# FRA_bulkhead_v2.net
KiCad netlist of a schematic drawn in EAGLE
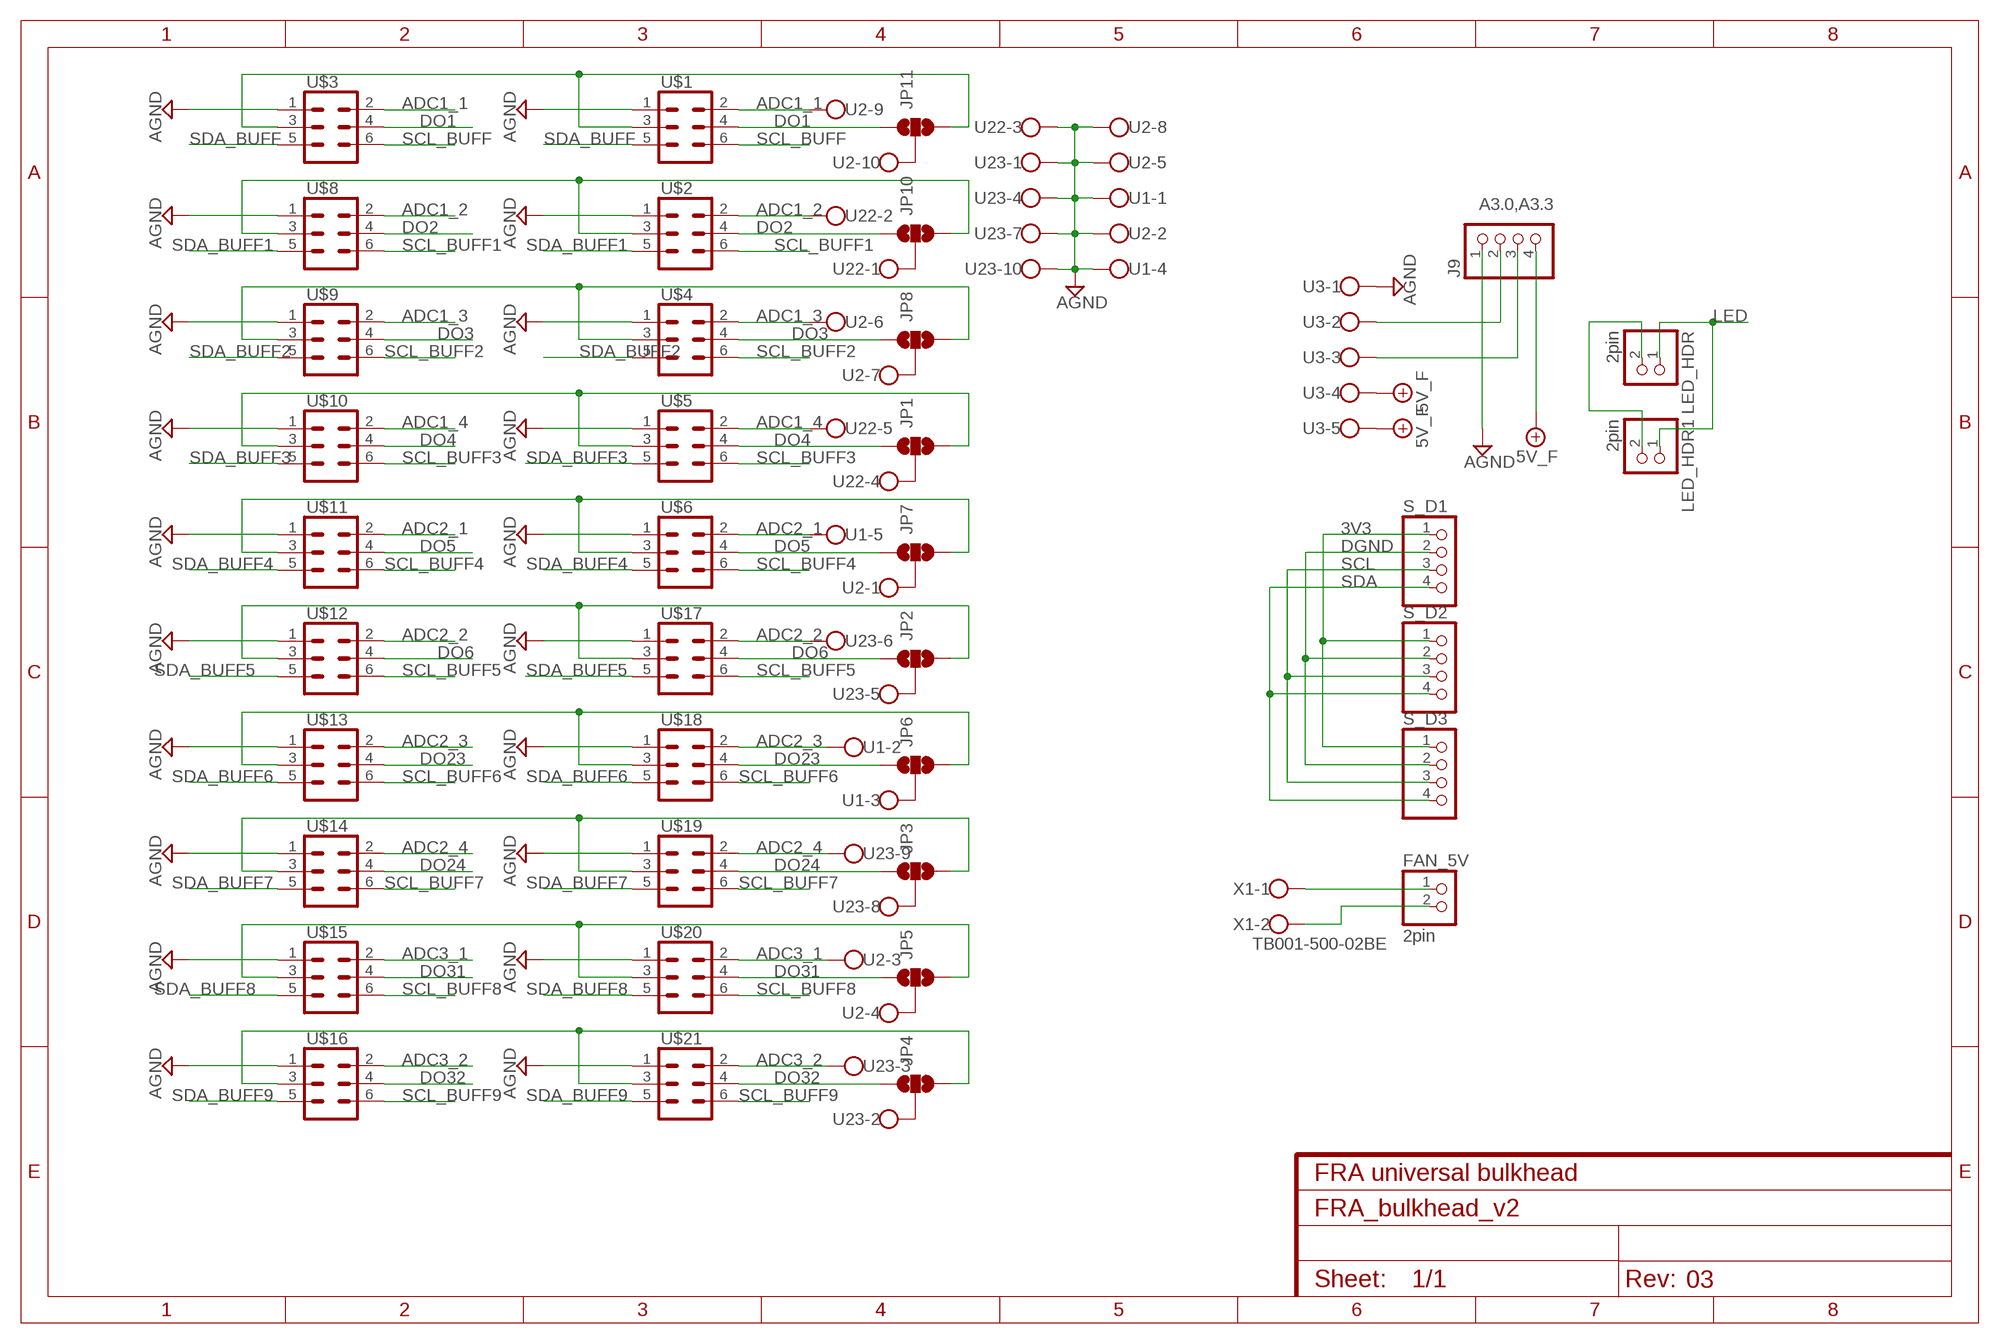
[diagram p0: schematic, sheet 1]

(export (version "E")
  (design (tool "Eeschema 10.0.6"))
  (components
    (comp (ref "FAN_5V")
      (value "2pin")
      (footprint "eagle-import:1X02")
      (fields (field (name "PARTNO") "TSW-102-07-G-S"))
      (libsource (lib "eagle-import") (part "PINHD-1X2"))
    )
    (comp (ref "J9")
      (value "4pin")
      (footprint "eagle-import:1X04")
      (fields (field (name "PARTNO") "61300411121"))
      (libsource (lib "eagle-import") (part "PINHD-1X4"))
    )
    (comp (ref "JP1")
      (value "JUMPER-SMT_3_NO_NO_SILK")
      (footprint "eagle-import:SMT-JUMPER_3_0-NO_TRACE_NO-SILK")
      (libsource (lib "eagle-import") (part "JUMPER-SMT_3_NO_NO_SILK"))
    )
    (comp (ref "JP2")
      (value "JUMPER-SMT_3_NO_NO_SILK")
      (footprint "eagle-import:SMT-JUMPER_3_0-NO_TRACE_NO-SILK")
      (libsource (lib "eagle-import") (part "JUMPER-SMT_3_NO_NO_SILK"))
    )
    (comp (ref "JP3")
      (value "JUMPER-SMT_3_NO_NO_SILK")
      (footprint "eagle-import:SMT-JUMPER_3_0-NO_TRACE_NO-SILK")
      (libsource (lib "eagle-import") (part "JUMPER-SMT_3_NO_NO_SILK"))
    )
    (comp (ref "JP4")
      (value "JUMPER-SMT_3_NO_NO_SILK")
      (footprint "eagle-import:SMT-JUMPER_3_0-NO_TRACE_NO-SILK")
      (libsource (lib "eagle-import") (part "JUMPER-SMT_3_NO_NO_SILK"))
    )
    (comp (ref "JP5")
      (value "JUMPER-SMT_3_NO_NO_SILK")
      (footprint "eagle-import:SMT-JUMPER_3_0-NO_TRACE_NO-SILK")
      (libsource (lib "eagle-import") (part "JUMPER-SMT_3_NO_NO_SILK"))
    )
    (comp (ref "JP6")
      (value "JUMPER-SMT_3_NO_NO_SILK")
      (footprint "eagle-import:SMT-JUMPER_3_0-NO_TRACE_NO-SILK")
      (libsource (lib "eagle-import") (part "JUMPER-SMT_3_NO_NO_SILK"))
    )
    (comp (ref "JP7")
      (value "JUMPER-SMT_3_NO_NO_SILK")
      (footprint "eagle-import:SMT-JUMPER_3_0-NO_TRACE_NO-SILK")
      (libsource (lib "eagle-import") (part "JUMPER-SMT_3_NO_NO_SILK"))
    )
    (comp (ref "JP8")
      (value "JUMPER-SMT_3_NO_NO_SILK")
      (footprint "eagle-import:SMT-JUMPER_3_0-NO_TRACE_NO-SILK")
      (libsource (lib "eagle-import") (part "JUMPER-SMT_3_NO_NO_SILK"))
    )
    (comp (ref "JP10")
      (value "JUMPER-SMT_3_NO_NO_SILK")
      (footprint "eagle-import:SMT-JUMPER_3_0-NO_TRACE_NO-SILK")
      (libsource (lib "eagle-import") (part "JUMPER-SMT_3_NO_NO_SILK"))
    )
    (comp (ref "JP11")
      (value "JUMPER-SMT_3_NO_NO_SILK")
      (footprint "eagle-import:SMT-JUMPER_3_0-NO_TRACE_NO-SILK")
      (libsource (lib "eagle-import") (part "JUMPER-SMT_3_NO_NO_SILK"))
    )
    (comp (ref "LED_HDR")
      (value "2pin")
      (footprint "eagle-import:1X02")
      (fields (field (name "PARTNO") "TSW-102-07-G-S"))
      (libsource (lib "eagle-import") (part "PINHD-1X2"))
    )
    (comp (ref "LED_HDR1")
      (value "2pin")
      (footprint "eagle-import:1X02")
      (fields (field (name "PARTNO") "TSW-102-07-G-S"))
      (libsource (lib "eagle-import") (part "PINHD-1X2"))
    )
    (comp (ref "S_D1")
      (value "4pin")
      (footprint "eagle-import:1X04")
      (fields (field (name "PARTNO") "61300411121"))
      (libsource (lib "eagle-import") (part "PINHD-1X4"))
    )
    (comp (ref "S_D2")
      (value "4pin")
      (footprint "eagle-import:1X04")
      (fields (field (name "PARTNO") "61300411121"))
      (libsource (lib "eagle-import") (part "PINHD-1X4"))
    )
    (comp (ref "S_D3")
      (value "4pin")
      (footprint "eagle-import:1X04")
      (fields (field (name "PARTNO") "61300411121"))
      (libsource (lib "eagle-import") (part "PINHD-1X4"))
    )
    (comp (ref "U$1")
      (value "CONN_03X2_WE_61200621621")
      (footprint "eagle-import:WE_61200621621")
      (fields (field (name "PARTNO") "61200621621"))
      (libsource (lib "eagle-import") (part "CONN_03X2_WE_61200621621"))
    )
    (comp (ref "U$2")
      (value "CONN_03X2_WE_61200621621")
      (footprint "eagle-import:WE_61200621621")
      (fields (field (name "PARTNO") "61200621621"))
      (libsource (lib "eagle-import") (part "CONN_03X2_WE_61200621621"))
    )
    (comp (ref "U$3")
      (value "CONN_03X2_WE_61200621621")
      (footprint "eagle-import:WE_61200621621")
      (fields (field (name "PARTNO") "61200621621"))
      (libsource (lib "eagle-import") (part "CONN_03X2_WE_61200621621"))
    )
    (comp (ref "U$4")
      (value "CONN_03X2_WE_61200621621")
      (footprint "eagle-import:WE_61200621621")
      (fields (field (name "PARTNO") "61200621621"))
      (libsource (lib "eagle-import") (part "CONN_03X2_WE_61200621621"))
    )
    (comp (ref "U$5")
      (value "CONN_03X2_WE_61200621621")
      (footprint "eagle-import:WE_61200621621")
      (fields (field (name "PARTNO") "61200621621"))
      (libsource (lib "eagle-import") (part "CONN_03X2_WE_61200621621"))
    )
    (comp (ref "U$6")
      (value "CONN_03X2_WE_61200621621")
      (footprint "eagle-import:WE_61200621621")
      (fields (field (name "PARTNO") "61200621621"))
      (libsource (lib "eagle-import") (part "CONN_03X2_WE_61200621621"))
    )
    (comp (ref "U$8")
      (value "CONN_03X2_WE_61200621621")
      (footprint "eagle-import:WE_61200621621")
      (fields (field (name "PARTNO") "61200621621"))
      (libsource (lib "eagle-import") (part "CONN_03X2_WE_61200621621"))
    )
    (comp (ref "U$9")
      (value "CONN_03X2_WE_61200621621")
      (footprint "eagle-import:WE_61200621621")
      (fields (field (name "PARTNO") "61200621621"))
      (libsource (lib "eagle-import") (part "CONN_03X2_WE_61200621621"))
    )
    (comp (ref "U$10")
      (value "CONN_03X2_WE_61200621621")
      (footprint "eagle-import:WE_61200621621")
      (fields (field (name "PARTNO") "61200621621"))
      (libsource (lib "eagle-import") (part "CONN_03X2_WE_61200621621"))
    )
    (comp (ref "U$11")
      (value "CONN_03X2_WE_61200621621")
      (footprint "eagle-import:WE_61200621621")
      (fields (field (name "PARTNO") "61200621621"))
      (libsource (lib "eagle-import") (part "CONN_03X2_WE_61200621621"))
    )
    (comp (ref "U$12")
      (value "CONN_03X2_WE_61200621621")
      (footprint "eagle-import:WE_61200621621")
      (fields (field (name "PARTNO") "61200621621"))
      (libsource (lib "eagle-import") (part "CONN_03X2_WE_61200621621"))
    )
    (comp (ref "U$13")
      (value "CONN_03X2_WE_61200621621")
      (footprint "eagle-import:WE_61200621621")
      (fields (field (name "PARTNO") "61200621621"))
      (libsource (lib "eagle-import") (part "CONN_03X2_WE_61200621621"))
    )
    (comp (ref "U$14")
      (value "CONN_03X2_WE_61200621621")
      (footprint "eagle-import:WE_61200621621")
      (fields (field (name "PARTNO") "61200621621"))
      (libsource (lib "eagle-import") (part "CONN_03X2_WE_61200621621"))
    )
    (comp (ref "U$15")
      (value "CONN_03X2_WE_61200621621")
      (footprint "eagle-import:WE_61200621621")
      (fields (field (name "PARTNO") "61200621621"))
      (libsource (lib "eagle-import") (part "CONN_03X2_WE_61200621621"))
    )
    (comp (ref "U$16")
      (value "CONN_03X2_WE_61200621621")
      (footprint "eagle-import:WE_61200621621")
      (fields (field (name "PARTNO") "61200621621"))
      (libsource (lib "eagle-import") (part "CONN_03X2_WE_61200621621"))
    )
    (comp (ref "U$17")
      (value "CONN_03X2_WE_61200621621")
      (footprint "eagle-import:WE_61200621621")
      (fields (field (name "PARTNO") "61200621621"))
      (libsource (lib "eagle-import") (part "CONN_03X2_WE_61200621621"))
    )
    (comp (ref "U$18")
      (value "CONN_03X2_WE_61200621621")
      (footprint "eagle-import:WE_61200621621")
      (fields (field (name "PARTNO") "61200621621"))
      (libsource (lib "eagle-import") (part "CONN_03X2_WE_61200621621"))
    )
    (comp (ref "U$19")
      (value "CONN_03X2_WE_61200621621")
      (footprint "eagle-import:WE_61200621621")
      (fields (field (name "PARTNO") "61200621621"))
      (libsource (lib "eagle-import") (part "CONN_03X2_WE_61200621621"))
    )
    (comp (ref "U$20")
      (value "CONN_03X2_WE_61200621621")
      (footprint "eagle-import:WE_61200621621")
      (fields (field (name "PARTNO") "61200621621"))
      (libsource (lib "eagle-import") (part "CONN_03X2_WE_61200621621"))
    )
    (comp (ref "U$21")
      (value "CONN_03X2_WE_61200621621")
      (footprint "eagle-import:WE_61200621621")
      (fields (field (name "PARTNO") "61200621621"))
      (libsource (lib "eagle-import") (part "CONN_03X2_WE_61200621621"))
    )
    (comp (ref "U1")
      (value "TB003V-500-P05BERIGHTANGLE-NORMAL")
      (footprint "eagle-import:TB003-500-P05BE")
      (libsource (lib "eagle-import") (part "TB003V-500-P05BERIGHTANGLE-NORMAL"))
    )
    (comp (ref "U2")
      (value "TB003V-500-P10BERIGHTANGLE-NORMAL")
      (footprint "eagle-import:TB003-500-P10BE")
      (libsource (lib "eagle-import") (part "TB003V-500-P10BERIGHTANGLE-NORMAL"))
    )
    (comp (ref "U3")
      (value "TB003V-500-P05BERIGHTANGLE-NORMAL")
      (footprint "eagle-import:TB003-500-P05BE")
      (libsource (lib "eagle-import") (part "TB003V-500-P05BERIGHTANGLE-NORMAL"))
    )
    (comp (ref "U22")
      (value "TB003V-500-P05BERIGHTANGLE-NORMAL")
      (footprint "eagle-import:TB003-500-P05BE")
      (libsource (lib "eagle-import") (part "TB003V-500-P05BERIGHTANGLE-NORMAL"))
    )
    (comp (ref "U23")
      (value "TB003V-500-P10BERIGHTANGLE-NORMAL")
      (footprint "eagle-import:TB003-500-P10BE")
      (libsource (lib "eagle-import") (part "TB003V-500-P10BERIGHTANGLE-NORMAL"))
    )
    (comp (ref "X1")
      (value "TB001-500-02BE")
      (footprint "eagle-import:W237-102")
      (fields (field (name "MPN") "237-102") (field (name "PARTNO") "TB001-500-02BE"))
      (libsource (lib "eagle-import") (part "W237-102"))
    )
  )
  (nets
    (net (code "1") (name "/3V3") (class "Default")
      (node (ref "S_D1") (pin "1") (pinfunction "1_1") (pintype "passive"))
      (node (ref "S_D2") (pin "1") (pinfunction "1_1") (pintype "passive"))
      (node (ref "S_D3") (pin "1") (pinfunction "1_1") (pintype "passive"))
    )
    (net (code "2") (name "/ADC1_1") (class "Default")
      (node (ref "U$1") (pin "2") (pinfunction "2_2") (pintype "bidirectional"))
      (node (ref "U$3") (pin "2") (pinfunction "2_2") (pintype "bidirectional"))
      (node (ref "U2") (pin "9") (pinfunction "KL_9") (pintype "passive"))
    )
    (net (code "3") (name "/ADC1_2") (class "Default")
      (node (ref "U$2") (pin "2") (pinfunction "2_2") (pintype "bidirectional"))
      (node (ref "U$8") (pin "2") (pinfunction "2_2") (pintype "bidirectional"))
      (node (ref "U22") (pin "2") (pinfunction "KL_2") (pintype "passive"))
    )
    (net (code "4") (name "/ADC1_3") (class "Default")
      (node (ref "U$4") (pin "2") (pinfunction "2_2") (pintype "bidirectional"))
      (node (ref "U$9") (pin "2") (pinfunction "2_2") (pintype "bidirectional"))
      (node (ref "U2") (pin "6") (pinfunction "KL_6") (pintype "passive"))
    )
    (net (code "5") (name "/ADC1_4") (class "Default")
      (node (ref "U$10") (pin "2") (pinfunction "2_2") (pintype "bidirectional"))
      (node (ref "U$5") (pin "2") (pinfunction "2_2") (pintype "bidirectional"))
      (node (ref "U22") (pin "5") (pinfunction "KL_5") (pintype "passive"))
    )
    (net (code "6") (name "/ADC2_1") (class "Default")
      (node (ref "U$11") (pin "2") (pinfunction "2_2") (pintype "bidirectional"))
      (node (ref "U$6") (pin "2") (pinfunction "2_2") (pintype "bidirectional"))
      (node (ref "U1") (pin "5") (pinfunction "KL_5") (pintype "passive"))
    )
    (net (code "7") (name "/ADC2_2") (class "Default")
      (node (ref "U$12") (pin "2") (pinfunction "2_2") (pintype "bidirectional"))
      (node (ref "U$17") (pin "2") (pinfunction "2_2") (pintype "bidirectional"))
      (node (ref "U23") (pin "6") (pinfunction "KL_6") (pintype "passive"))
    )
    (net (code "8") (name "/ADC2_3") (class "Default")
      (node (ref "U$13") (pin "2") (pinfunction "2_2") (pintype "bidirectional"))
      (node (ref "U$18") (pin "2") (pinfunction "2_2") (pintype "bidirectional"))
      (node (ref "U1") (pin "2") (pinfunction "KL_2") (pintype "passive"))
    )
    (net (code "9") (name "/ADC2_4") (class "Default")
      (node (ref "U$14") (pin "2") (pinfunction "2_2") (pintype "bidirectional"))
      (node (ref "U$19") (pin "2") (pinfunction "2_2") (pintype "bidirectional"))
      (node (ref "U23") (pin "9") (pinfunction "KL_9") (pintype "passive"))
    )
    (net (code "10") (name "/ADC3_1") (class "Default")
      (node (ref "U$15") (pin "2") (pinfunction "2_2") (pintype "bidirectional"))
      (node (ref "U$20") (pin "2") (pinfunction "2_2") (pintype "bidirectional"))
      (node (ref "U2") (pin "3") (pinfunction "KL_3") (pintype "passive"))
    )
    (net (code "11") (name "/ADC3_2") (class "Default")
      (node (ref "U$16") (pin "2") (pinfunction "2_2") (pintype "bidirectional"))
      (node (ref "U$21") (pin "2") (pinfunction "2_2") (pintype "bidirectional"))
      (node (ref "U23") (pin "3") (pinfunction "KL_3") (pintype "passive"))
    )
    (net (code "12") (name "/DGND") (class "Default")
      (node (ref "S_D1") (pin "2") (pinfunction "2_2") (pintype "passive"))
      (node (ref "S_D2") (pin "2") (pinfunction "2_2") (pintype "passive"))
      (node (ref "S_D3") (pin "2") (pinfunction "2_2") (pintype "passive"))
    )
    (net (code "13") (name "/DO1") (class "Default")
      (node (ref "JP11") (pin "1") (pinfunction "1_1") (pintype "passive"))
      (node (ref "U$1") (pin "4") (pinfunction "4_4") (pintype "bidirectional"))
      (node (ref "U$3") (pin "4") (pinfunction "4_4") (pintype "bidirectional"))
    )
    (net (code "14") (name "/DO2") (class "Default")
      (node (ref "JP10") (pin "1") (pinfunction "1_1") (pintype "passive"))
      (node (ref "U$2") (pin "4") (pinfunction "4_4") (pintype "bidirectional"))
      (node (ref "U$8") (pin "4") (pinfunction "4_4") (pintype "bidirectional"))
    )
    (net (code "15") (name "/DO3") (class "Default")
      (node (ref "JP8") (pin "1") (pinfunction "1_1") (pintype "passive"))
      (node (ref "U$4") (pin "4") (pinfunction "4_4") (pintype "bidirectional"))
      (node (ref "U$9") (pin "4") (pinfunction "4_4") (pintype "bidirectional"))
    )
    (net (code "16") (name "/DO4") (class "Default")
      (node (ref "JP1") (pin "1") (pinfunction "1_1") (pintype "passive"))
      (node (ref "U$10") (pin "4") (pinfunction "4_4") (pintype "bidirectional"))
      (node (ref "U$5") (pin "4") (pinfunction "4_4") (pintype "bidirectional"))
    )
    (net (code "17") (name "/DO5") (class "Default")
      (node (ref "JP7") (pin "1") (pinfunction "1_1") (pintype "passive"))
      (node (ref "U$11") (pin "4") (pinfunction "4_4") (pintype "bidirectional"))
      (node (ref "U$6") (pin "4") (pinfunction "4_4") (pintype "bidirectional"))
    )
    (net (code "18") (name "/DO6") (class "Default")
      (node (ref "JP2") (pin "1") (pinfunction "1_1") (pintype "passive"))
      (node (ref "U$12") (pin "4") (pinfunction "4_4") (pintype "bidirectional"))
      (node (ref "U$17") (pin "4") (pinfunction "4_4") (pintype "bidirectional"))
    )
    (net (code "19") (name "/DO23") (class "Default")
      (node (ref "JP6") (pin "1") (pinfunction "1_1") (pintype "passive"))
      (node (ref "U$13") (pin "4") (pinfunction "4_4") (pintype "bidirectional"))
      (node (ref "U$18") (pin "4") (pinfunction "4_4") (pintype "bidirectional"))
    )
    (net (code "20") (name "/DO24") (class "Default")
      (node (ref "JP3") (pin "1") (pinfunction "1_1") (pintype "passive"))
      (node (ref "U$14") (pin "4") (pinfunction "4_4") (pintype "bidirectional"))
      (node (ref "U$19") (pin "4") (pinfunction "4_4") (pintype "bidirectional"))
    )
    (net (code "21") (name "/DO31") (class "Default")
      (node (ref "JP5") (pin "1") (pinfunction "1_1") (pintype "passive"))
      (node (ref "U$15") (pin "4") (pinfunction "4_4") (pintype "bidirectional"))
      (node (ref "U$20") (pin "4") (pinfunction "4_4") (pintype "bidirectional"))
    )
    (net (code "22") (name "/DO32") (class "Default")
      (node (ref "JP4") (pin "1") (pinfunction "1_1") (pintype "passive"))
      (node (ref "U$16") (pin "4") (pinfunction "4_4") (pintype "bidirectional"))
      (node (ref "U$21") (pin "4") (pinfunction "4_4") (pintype "bidirectional"))
    )
    (net (code "23") (name "/LED") (class "Default")
      (node (ref "LED_HDR") (pin "1") (pinfunction "1_1") (pintype "passive"))
      (node (ref "LED_HDR1") (pin "1") (pinfunction "1_1") (pintype "passive"))
    )
    (net (code "24") (name "/SCL") (class "Default")
      (node (ref "S_D1") (pin "3") (pinfunction "3_3") (pintype "passive"))
      (node (ref "S_D2") (pin "3") (pinfunction "3_3") (pintype "passive"))
      (node (ref "S_D3") (pin "3") (pinfunction "3_3") (pintype "passive"))
    )
    (net (code "25") (name "/SCL_BUFF") (class "Default")
      (node (ref "U$1") (pin "6") (pinfunction "6_6") (pintype "bidirectional"))
      (node (ref "U$3") (pin "6") (pinfunction "6_6") (pintype "bidirectional"))
    )
    (net (code "26") (name "/SCL_BUFF1") (class "Default")
      (node (ref "U$2") (pin "6") (pinfunction "6_6") (pintype "bidirectional"))
      (node (ref "U$8") (pin "6") (pinfunction "6_6") (pintype "bidirectional"))
    )
    (net (code "27") (name "/SCL_BUFF2") (class "Default")
      (node (ref "U$4") (pin "6") (pinfunction "6_6") (pintype "bidirectional"))
      (node (ref "U$9") (pin "6") (pinfunction "6_6") (pintype "bidirectional"))
    )
    (net (code "28") (name "/SCL_BUFF3") (class "Default")
      (node (ref "U$10") (pin "6") (pinfunction "6_6") (pintype "bidirectional"))
      (node (ref "U$5") (pin "6") (pinfunction "6_6") (pintype "bidirectional"))
    )
    (net (code "29") (name "/SCL_BUFF4") (class "Default")
      (node (ref "U$11") (pin "6") (pinfunction "6_6") (pintype "bidirectional"))
      (node (ref "U$6") (pin "6") (pinfunction "6_6") (pintype "bidirectional"))
    )
    (net (code "30") (name "/SCL_BUFF5") (class "Default")
      (node (ref "U$12") (pin "6") (pinfunction "6_6") (pintype "bidirectional"))
      (node (ref "U$17") (pin "6") (pinfunction "6_6") (pintype "bidirectional"))
    )
    (net (code "31") (name "/SCL_BUFF6") (class "Default")
      (node (ref "U$13") (pin "6") (pinfunction "6_6") (pintype "bidirectional"))
      (node (ref "U$18") (pin "6") (pinfunction "6_6") (pintype "bidirectional"))
    )
    (net (code "32") (name "/SCL_BUFF7") (class "Default")
      (node (ref "U$14") (pin "6") (pinfunction "6_6") (pintype "bidirectional"))
      (node (ref "U$19") (pin "6") (pinfunction "6_6") (pintype "bidirectional"))
    )
    (net (code "33") (name "/SCL_BUFF8") (class "Default")
      (node (ref "U$15") (pin "6") (pinfunction "6_6") (pintype "bidirectional"))
      (node (ref "U$20") (pin "6") (pinfunction "6_6") (pintype "bidirectional"))
    )
    (net (code "34") (name "/SCL_BUFF9") (class "Default")
      (node (ref "U$16") (pin "6") (pinfunction "6_6") (pintype "bidirectional"))
      (node (ref "U$21") (pin "6") (pinfunction "6_6") (pintype "bidirectional"))
    )
    (net (code "35") (name "/SDA") (class "Default")
      (node (ref "S_D1") (pin "4") (pinfunction "4_4") (pintype "passive"))
      (node (ref "S_D2") (pin "4") (pinfunction "4_4") (pintype "passive"))
      (node (ref "S_D3") (pin "4") (pinfunction "4_4") (pintype "passive"))
    )
    (net (code "36") (name "/SDA_BUFF") (class "Default")
      (node (ref "U$1") (pin "5") (pinfunction "5_5") (pintype "bidirectional"))
      (node (ref "U$3") (pin "5") (pinfunction "5_5") (pintype "bidirectional"))
    )
    (net (code "37") (name "/SDA_BUFF1") (class "Default")
      (node (ref "U$2") (pin "5") (pinfunction "5_5") (pintype "bidirectional"))
      (node (ref "U$8") (pin "5") (pinfunction "5_5") (pintype "bidirectional"))
    )
    (net (code "38") (name "/SDA_BUFF2") (class "Default")
      (node (ref "U$4") (pin "5") (pinfunction "5_5") (pintype "bidirectional"))
      (node (ref "U$9") (pin "5") (pinfunction "5_5") (pintype "bidirectional"))
    )
    (net (code "39") (name "/SDA_BUFF3") (class "Default")
      (node (ref "U$10") (pin "5") (pinfunction "5_5") (pintype "bidirectional"))
      (node (ref "U$5") (pin "5") (pinfunction "5_5") (pintype "bidirectional"))
    )
    (net (code "40") (name "/SDA_BUFF4") (class "Default")
      (node (ref "U$11") (pin "5") (pinfunction "5_5") (pintype "bidirectional"))
      (node (ref "U$6") (pin "5") (pinfunction "5_5") (pintype "bidirectional"))
    )
    (net (code "41") (name "/SDA_BUFF5") (class "Default")
      (node (ref "U$12") (pin "5") (pinfunction "5_5") (pintype "bidirectional"))
      (node (ref "U$17") (pin "5") (pinfunction "5_5") (pintype "bidirectional"))
    )
    (net (code "42") (name "/SDA_BUFF6") (class "Default")
      (node (ref "U$13") (pin "5") (pinfunction "5_5") (pintype "bidirectional"))
      (node (ref "U$18") (pin "5") (pinfunction "5_5") (pintype "bidirectional"))
    )
    (net (code "43") (name "/SDA_BUFF7") (class "Default")
      (node (ref "U$14") (pin "5") (pinfunction "5_5") (pintype "bidirectional"))
      (node (ref "U$19") (pin "5") (pinfunction "5_5") (pintype "bidirectional"))
    )
    (net (code "44") (name "/SDA_BUFF8") (class "Default")
      (node (ref "U$15") (pin "5") (pinfunction "5_5") (pintype "bidirectional"))
      (node (ref "U$20") (pin "5") (pinfunction "5_5") (pintype "bidirectional"))
    )
    (net (code "45") (name "/SDA_BUFF9") (class "Default")
      (node (ref "U$16") (pin "5") (pinfunction "5_5") (pintype "bidirectional"))
      (node (ref "U$21") (pin "5") (pinfunction "5_5") (pintype "bidirectional"))
    )
    (net (code "46") (name "5V_F") (class "Default")
      (node (ref "J9") (pin "4") (pinfunction "4_4") (pintype "passive"))
      (node (ref "U3") (pin "4") (pinfunction "KL_4") (pintype "passive"))
      (node (ref "U3") (pin "5") (pinfunction "KL_5") (pintype "passive"))
    )
    (net (code "47") (name "AGND") (class "Default")
      (node (ref "J9") (pin "1") (pinfunction "1_1") (pintype "passive"))
      (node (ref "U$1") (pin "1") (pinfunction "1_1") (pintype "bidirectional"))
      (node (ref "U$10") (pin "1") (pinfunction "1_1") (pintype "bidirectional"))
      (node (ref "U$11") (pin "1") (pinfunction "1_1") (pintype "bidirectional"))
      (node (ref "U$12") (pin "1") (pinfunction "1_1") (pintype "bidirectional"))
      (node (ref "U$13") (pin "1") (pinfunction "1_1") (pintype "bidirectional"))
      (node (ref "U$14") (pin "1") (pinfunction "1_1") (pintype "bidirectional"))
      (node (ref "U$15") (pin "1") (pinfunction "1_1") (pintype "bidirectional"))
      (node (ref "U$16") (pin "1") (pinfunction "1_1") (pintype "bidirectional"))
      (node (ref "U$17") (pin "1") (pinfunction "1_1") (pintype "bidirectional"))
      (node (ref "U$18") (pin "1") (pinfunction "1_1") (pintype "bidirectional"))
      (node (ref "U$19") (pin "1") (pinfunction "1_1") (pintype "bidirectional"))
      (node (ref "U$2") (pin "1") (pinfunction "1_1") (pintype "bidirectional"))
      (node (ref "U$20") (pin "1") (pinfunction "1_1") (pintype "bidirectional"))
      (node (ref "U$21") (pin "1") (pinfunction "1_1") (pintype "bidirectional"))
      (node (ref "U$3") (pin "1") (pinfunction "1_1") (pintype "bidirectional"))
      (node (ref "U$4") (pin "1") (pinfunction "1_1") (pintype "bidirectional"))
      (node (ref "U$5") (pin "1") (pinfunction "1_1") (pintype "bidirectional"))
      (node (ref "U$6") (pin "1") (pinfunction "1_1") (pintype "bidirectional"))
      (node (ref "U$8") (pin "1") (pinfunction "1_1") (pintype "bidirectional"))
      (node (ref "U$9") (pin "1") (pinfunction "1_1") (pintype "bidirectional"))
      (node (ref "U1") (pin "1") (pinfunction "KL_1") (pintype "passive"))
      (node (ref "U1") (pin "4") (pinfunction "KL_4") (pintype "passive"))
      (node (ref "U2") (pin "2") (pinfunction "KL_2") (pintype "passive"))
      (node (ref "U2") (pin "5") (pinfunction "KL_5") (pintype "passive"))
      (node (ref "U2") (pin "8") (pinfunction "KL_8") (pintype "passive"))
      (node (ref "U22") (pin "3") (pinfunction "KL_3") (pintype "passive"))
      (node (ref "U23") (pin "1") (pinfunction "KL_1") (pintype "passive"))
      (node (ref "U23") (pin "10") (pinfunction "KL_10") (pintype "passive"))
      (node (ref "U23") (pin "4") (pinfunction "KL_4") (pintype "passive"))
      (node (ref "U23") (pin "7") (pinfunction "KL_7") (pintype "passive"))
      (node (ref "U3") (pin "1") (pinfunction "KL_1") (pintype "passive"))
    )
    (net (code "48") (name "Net-(JP1-Pad3)") (class "Default")
      (node (ref "JP1") (pin "3") (pinfunction "3_3") (pintype "passive"))
      (node (ref "U$10") (pin "3") (pinfunction "3_3") (pintype "bidirectional"))
      (node (ref "U$5") (pin "3") (pinfunction "3_3") (pintype "bidirectional"))
    )
    (net (code "49") (name "Net-(JP2-Pad3)") (class "Default")
      (node (ref "JP2") (pin "3") (pinfunction "3_3") (pintype "passive"))
      (node (ref "U$12") (pin "3") (pinfunction "3_3") (pintype "bidirectional"))
      (node (ref "U$17") (pin "3") (pinfunction "3_3") (pintype "bidirectional"))
    )
    (net (code "50") (name "Net-(JP3-Pad3)") (class "Default")
      (node (ref "JP3") (pin "3") (pinfunction "3_3") (pintype "passive"))
      (node (ref "U$14") (pin "3") (pinfunction "3_3") (pintype "bidirectional"))
      (node (ref "U$19") (pin "3") (pinfunction "3_3") (pintype "bidirectional"))
    )
    (net (code "51") (name "Net-(JP4-Pad3)") (class "Default")
      (node (ref "JP4") (pin "3") (pinfunction "3_3") (pintype "passive"))
      (node (ref "U$16") (pin "3") (pinfunction "3_3") (pintype "bidirectional"))
      (node (ref "U$21") (pin "3") (pinfunction "3_3") (pintype "bidirectional"))
    )
    (net (code "52") (name "Net-(JP5-Pad3)") (class "Default")
      (node (ref "JP5") (pin "3") (pinfunction "3_3") (pintype "passive"))
      (node (ref "U$15") (pin "3") (pinfunction "3_3") (pintype "bidirectional"))
      (node (ref "U$20") (pin "3") (pinfunction "3_3") (pintype "bidirectional"))
    )
    (net (code "53") (name "Net-(JP6-Pad3)") (class "Default")
      (node (ref "JP6") (pin "3") (pinfunction "3_3") (pintype "passive"))
      (node (ref "U$13") (pin "3") (pinfunction "3_3") (pintype "bidirectional"))
      (node (ref "U$18") (pin "3") (pinfunction "3_3") (pintype "bidirectional"))
    )
    (net (code "54") (name "Net-(JP7-Pad3)") (class "Default")
      (node (ref "JP7") (pin "3") (pinfunction "3_3") (pintype "passive"))
      (node (ref "U$11") (pin "3") (pinfunction "3_3") (pintype "bidirectional"))
      (node (ref "U$6") (pin "3") (pinfunction "3_3") (pintype "bidirectional"))
    )
    (net (code "55") (name "Net-(JP8-Pad3)") (class "Default")
      (node (ref "JP8") (pin "3") (pinfunction "3_3") (pintype "passive"))
      (node (ref "U$4") (pin "3") (pinfunction "3_3") (pintype "bidirectional"))
      (node (ref "U$9") (pin "3") (pinfunction "3_3") (pintype "bidirectional"))
    )
    (net (code "56") (name "Net-(JP10-Pad3)") (class "Default")
      (node (ref "JP10") (pin "3") (pinfunction "3_3") (pintype "passive"))
      (node (ref "U$2") (pin "3") (pinfunction "3_3") (pintype "bidirectional"))
      (node (ref "U$8") (pin "3") (pinfunction "3_3") (pintype "bidirectional"))
    )
    (net (code "57") (name "Net-(JP11-Pad3)") (class "Default")
      (node (ref "JP11") (pin "3") (pinfunction "3_3") (pintype "passive"))
      (node (ref "U$1") (pin "3") (pinfunction "3_3") (pintype "bidirectional"))
      (node (ref "U$3") (pin "3") (pinfunction "3_3") (pintype "bidirectional"))
    )
    (net (code "58") (name "Net-(LED_HDR-Pad2)") (class "Default")
      (node (ref "LED_HDR") (pin "2") (pinfunction "2_2") (pintype "passive"))
      (node (ref "LED_HDR1") (pin "2") (pinfunction "2_2") (pintype "passive"))
    )
    (net (code "59") (name "Net-(U1C-KL)") (class "Default")
      (node (ref "JP6") (pin "2") (pinfunction "2_2") (pintype "passive"))
      (node (ref "U1") (pin "3") (pinfunction "KL_3") (pintype "passive"))
    )
    (net (code "60") (name "Net-(U2A-KL)") (class "Default")
      (node (ref "JP7") (pin "2") (pinfunction "2_2") (pintype "passive"))
      (node (ref "U2") (pin "1") (pinfunction "KL_1") (pintype "passive"))
    )
    (net (code "61") (name "Net-(U2B-KL)") (class "Default")
      (node (ref "JP11") (pin "2") (pinfunction "2_2") (pintype "passive"))
      (node (ref "U2") (pin "10") (pinfunction "KL_10") (pintype "passive"))
    )
    (net (code "62") (name "Net-(U2E-KL)") (class "Default")
      (node (ref "JP5") (pin "2") (pinfunction "2_2") (pintype "passive"))
      (node (ref "U2") (pin "4") (pinfunction "KL_4") (pintype "passive"))
    )
    (net (code "63") (name "Net-(U2H-KL)") (class "Default")
      (node (ref "JP8") (pin "2") (pinfunction "2_2") (pintype "passive"))
      (node (ref "U2") (pin "7") (pinfunction "KL_7") (pintype "passive"))
    )
    (net (code "64") (name "Net-(U3B-KL)") (class "Default")
      (node (ref "J9") (pin "2") (pinfunction "2_2") (pintype "passive"))
      (node (ref "U3") (pin "2") (pinfunction "KL_2") (pintype "passive"))
    )
    (net (code "65") (name "Net-(U3C-KL)") (class "Default")
      (node (ref "J9") (pin "3") (pinfunction "3_3") (pintype "passive"))
      (node (ref "U3") (pin "3") (pinfunction "KL_3") (pintype "passive"))
    )
    (net (code "66") (name "Net-(U22A-KL)") (class "Default")
      (node (ref "JP10") (pin "2") (pinfunction "2_2") (pintype "passive"))
      (node (ref "U22") (pin "1") (pinfunction "KL_1") (pintype "passive"))
    )
    (net (code "67") (name "Net-(U22D-KL)") (class "Default")
      (node (ref "JP1") (pin "2") (pinfunction "2_2") (pintype "passive"))
      (node (ref "U22") (pin "4") (pinfunction "KL_4") (pintype "passive"))
    )
    (net (code "68") (name "Net-(U23C-KL)") (class "Default")
      (node (ref "JP4") (pin "2") (pinfunction "2_2") (pintype "passive"))
      (node (ref "U23") (pin "2") (pinfunction "KL_2") (pintype "passive"))
    )
    (net (code "69") (name "Net-(U23F-KL)") (class "Default")
      (node (ref "JP2") (pin "2") (pinfunction "2_2") (pintype "passive"))
      (node (ref "U23") (pin "5") (pinfunction "KL_5") (pintype "passive"))
    )
    (net (code "70") (name "Net-(U23I-KL)") (class "Default")
      (node (ref "JP3") (pin "2") (pinfunction "2_2") (pintype "passive"))
      (node (ref "U23") (pin "8") (pinfunction "KL_8") (pintype "passive"))
    )
    (net (code "71") (name "Net-(X1A-KL)") (class "Default")
      (node (ref "FAN_5V") (pin "1") (pinfunction "1_1") (pintype "passive"))
      (node (ref "X1") (pin "1") (pinfunction "KL_1") (pintype "passive"))
    )
    (net (code "72") (name "Net-(X1B-KL)") (class "Default")
      (node (ref "FAN_5V") (pin "2") (pinfunction "2_2") (pintype "passive"))
      (node (ref "X1") (pin "2") (pinfunction "KL_2") (pintype "passive"))
    )
  )
)
